# MC33886_driver_board.net
KiCad netlist of a schematic drawn in Altium Designer
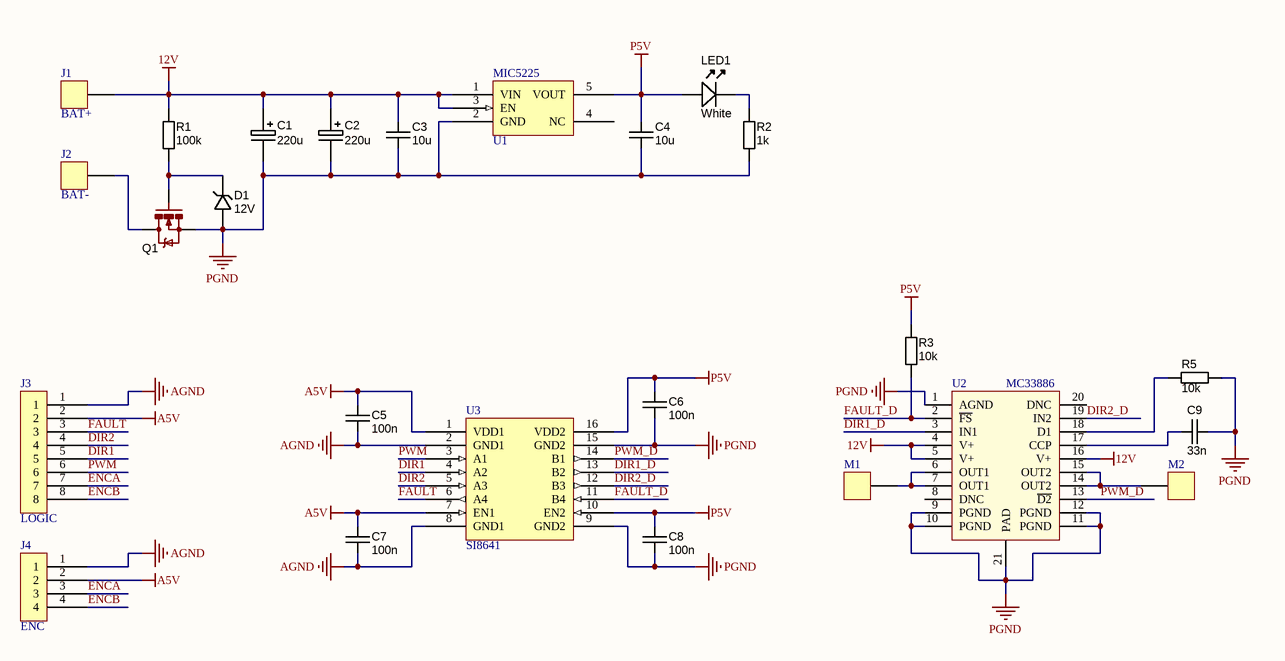
[diagram p0: MC33886_driver_board.SchDoc]

(export (version "E")
  (design (tool "Eeschema 10.0.6"))
  (components
    (comp (ref "C1")
      (value "220u")
      (footprint "CAPE3.5mm")
      (description "Capacitor THT Alum Elec 220uF 20% 16V")
      (fields (field (name "TOLERANCE") "±20%"))
      (libsource (lib "PBL - Capacitors") (part "CAPE_220u_16V_THD"))
    )
    (comp (ref "C2")
      (value "220u")
      (footprint "CAPE3.5mm")
      (description "Capacitor THT Alum Elec 220uF 20% 16V")
      (fields (field (name "TOLERANCE") "±20%"))
      (libsource (lib "PBL - Capacitors") (part "CAPE_220u_16V_THD"))
    )
    (comp (ref "C3")
      (value "10u")
      (footprint "CAPC3216X180N")
      (description "Capacitor SMD Cer 10uF 10% 16V X7R 1206")
      (fields (field (name "TOLERANCE") "±10%"))
      (libsource (lib "PBL - Capacitors") (part "CAPC_10u_1206_16V"))
    )
    (comp (ref "C4")
      (value "10u")
      (footprint "CAPC3216X180N")
      (description "Capacitor SMD Cer 10uF 10% 16V X7R 1206")
      (fields (field (name "TOLERANCE") "±10%"))
      (libsource (lib "PBL - Capacitors") (part "CAPC_10u_1206_16V"))
    )
    (comp (ref "C5")
      (value "100n")
      (footprint "CAPC1608X90N")
      (description "Capacitor SMD Cer 10nF 10% 50V X7R 0603")
      (fields (field (name "TOLERANCE") "±10%"))
      (libsource (lib "PBL - Capacitors") (part "CAPC_10n_0603_X7R_50V_10%"))
    )
    (comp (ref "C6")
      (value "100n")
      (footprint "CAPC1608X90N")
      (description "Capacitor SMD Cer 10nF 10% 50V X7R 0603")
      (fields (field (name "TOLERANCE") "±10%"))
      (libsource (lib "PBL - Capacitors") (part "CAPC_10n_0603_X7R_50V_10%"))
    )
    (comp (ref "C7")
      (value "100n")
      (footprint "CAPC1608X90N")
      (description "Capacitor SMD Cer 10nF 10% 50V X7R 0603")
      (fields (field (name "TOLERANCE") "±10%"))
      (libsource (lib "PBL - Capacitors") (part "CAPC_10n_0603_X7R_50V_10%"))
    )
    (comp (ref "C8")
      (value "100n")
      (footprint "CAPC1608X90N")
      (description "Capacitor SMD Cer 10nF 10% 50V X7R 0603")
      (fields (field (name "TOLERANCE") "±10%"))
      (libsource (lib "PBL - Capacitors") (part "CAPC_10n_0603_X7R_50V_10%"))
    )
    (comp (ref "C9")
      (value "33n")
      (footprint "CAPC1608X90N")
      (description "Capacitor SMD Cer 10nF 10% 50V X7R 0603")
      (fields (field (name "TOLERANCE") "±10%"))
      (libsource (lib "PBL - Capacitors") (part "CAPC_10n_0603_X7R_50V_10%"))
    )
    (comp (ref "D1")
      (value "12V")
      (footprint "SOD123")
      (description "Diode Zener SMD 28V 0.5W SOD-123")
      (fields (field (name "TOLERANCE") "±5%"))
      (libsource (lib "PBL - Diodes") (part "DIODE_ZENER_28V_500mW"))
    )
    (comp (ref "J1") (value "BAT+") (footprint "POWER-PAD") (libsource (lib "connectors") (part "HEADER-1")))
    (comp (ref "J2") (value "BAT-") (footprint "POWER-PAD") (libsource (lib "connectors") (part "HEADER-1")))
    (comp (ref "J3")
      (value "LOGIC")
      (footprint "MICRO-MATCH-8")
      (libsource (lib "connectors") (part "HEADER-8"))
    )
    (comp (ref "J4")
      (value "ENC")
      (footprint "MICRO-MATCH-4")
      (libsource (lib "connectors") (part "HEADER-4"))
    )
    (comp (ref "LED1")
      (value "White")
      (footprint "LED-0603-GREEN")
      (description "LED 0603 SMD Green 570nm 50mcd 20mA")
      (libsource (lib "PBL - Light Sources") (part "LED_SMD_Green_0603_570nm"))
    )
    (comp (ref "M1")
      (value "HEADER-1")
      (footprint "POWER-PAD")
      (libsource (lib "connectors") (part "HEADER-1"))
    )
    (comp (ref "M2") (value "HEADER-1") (footprint "POWER-PAD") (libsource (lib "") (part "HEADER-1_1")))
    (comp (ref "Q1") (value "MOSFET-N") (footprint "SOT669") (libsource (lib "mosfets") (part "MOSFET-N")))
    (comp (ref "R1")
      (value "100k")
      (footprint "RESC1608X55N")
      (description "Resistor SMD chip 1k Ohm 0.1W 1% 0603")
      (fields (field (name "TOLERANCE") "±1%"))
      (libsource (lib "PBL - Resistors") (part "RES_1K_0603_1%"))
    )
    (comp (ref "R2")
      (value "1k")
      (footprint "RESC1608X55N")
      (description "Resistor SMD chip 1k Ohm 0.1W 1% 0603")
      (fields (field (name "TOLERANCE") "±1%"))
      (libsource (lib "PBL - Resistors") (part "RES_1K_0603_1%"))
    )
    (comp (ref "R3")
      (value "10k")
      (footprint "RESC1608X55N")
      (description "Resistor SMD chip 1k Ohm 0.1W 1% 0603")
      (fields (field (name "TOLERANCE") "±1%"))
      (libsource (lib "PBL - Resistors") (part "RES_1K_0603_1%"))
    )
    (comp (ref "R5")
      (value "10k")
      (footprint "RESC1608X55N")
      (description "Resistor SMD chip 1k Ohm 0.1W 1% 0603")
      (fields (field (name "TOLERANCE") "±1%"))
      (libsource (lib "") (part "RES_1K_0603_1%_1"))
    )
    (comp (ref "U1") (value "MIC5225") (footprint "SOT23-5") (libsource (lib "power") (part "LDO-SOT23-5")))
    (comp (ref "U2")
      (value "MC33886")
      (footprint "MC33886")
      (libsource (lib "motor_drivers") (part "MC33886"))
    )
    (comp (ref "U3") (value "SI8641") (footprint "SOIC16") (libsource (lib "digital") (part "SI8641")))
  )
  (nets
    (net (code "1") (name "/DIR1") (class "Default")
      (node (ref "J3") (pin "5") (pinfunction "5_5") (pintype "passive"))
      (node (ref "U3") (pin "4") (pinfunction "A2_4") (pintype "input"))
    )
    (net (code "2") (name "/DIR1_D") (class "Default")
      (node (ref "U2") (pin "3") (pinfunction "IN1_3") (pintype "passive"))
      (node (ref "U3") (pin "13") (pinfunction "B2_13") (pintype "output"))
    )
    (net (code "3") (name "/DIR2") (class "Default")
      (node (ref "J3") (pin "4") (pinfunction "4_4") (pintype "passive"))
      (node (ref "U3") (pin "5") (pinfunction "A3_5") (pintype "input"))
    )
    (net (code "4") (name "/DIR2_D") (class "Default")
      (node (ref "U2") (pin "19") (pinfunction "IN2_19") (pintype "passive"))
      (node (ref "U3") (pin "12") (pinfunction "B3_12") (pintype "output"))
    )
    (net (code "5") (name "/ENCA") (class "Default")
      (node (ref "J3") (pin "7") (pinfunction "7_7") (pintype "passive"))
      (node (ref "J4") (pin "3") (pinfunction "3_3") (pintype "passive"))
    )
    (net (code "6") (name "/ENCB") (class "Default")
      (node (ref "J3") (pin "8") (pinfunction "8_8") (pintype "passive"))
      (node (ref "J4") (pin "4") (pinfunction "4_4") (pintype "passive"))
    )
    (net (code "7") (name "/FAULT") (class "Default")
      (node (ref "J3") (pin "3") (pinfunction "3_3") (pintype "passive"))
      (node (ref "U3") (pin "6") (pinfunction "A4_6") (pintype "output"))
    )
    (net (code "8") (name "/FAULT_D") (class "Default")
      (node (ref "R3") (pin "2") (pinfunction "2_2") (pintype "passive"))
      (node (ref "U2") (pin "2") (pinfunction "~{FS}_2") (pintype "passive"))
      (node (ref "U3") (pin "11") (pinfunction "B4_11") (pintype "input"))
    )
    (net (code "9") (name "/PWM") (class "Default")
      (node (ref "J3") (pin "6") (pinfunction "6_6") (pintype "passive"))
      (node (ref "U3") (pin "3") (pinfunction "A1_3") (pintype "input"))
    )
    (net (code "10") (name "/PWM_D") (class "Default")
      (node (ref "U2") (pin "13") (pinfunction "~{D2}_13") (pintype "passive"))
      (node (ref "U3") (pin "14") (pinfunction "B1_14") (pintype "output"))
    )
    (net (code "11") (name "12V") (class "Default")
      (node (ref "C1") (pin "1") (pintype "passive"))
      (node (ref "C2") (pin "1") (pintype "passive"))
      (node (ref "C3") (pin "1") (pintype "passive"))
      (node (ref "J1") (pin "1") (pinfunction "1_1") (pintype "passive"))
      (node (ref "R1") (pin "1") (pinfunction "1_1") (pintype "passive"))
      (node (ref "U1") (pin "1") (pinfunction "VIN_1") (pintype "power_in"))
      (node (ref "U1") (pin "3") (pinfunction "EN_3") (pintype "input"))
      (node (ref "U2") (pin "16") (pinfunction "V+_16") (pintype "passive"))
      (node (ref "U2") (pin "4") (pinfunction "V+_4") (pintype "passive"))
      (node (ref "U2") (pin "5") (pinfunction "V+_5") (pintype "passive"))
    )
    (net (code "12") (name "A5V") (class "Default")
      (node (ref "C5") (pin "2") (pintype "passive"))
      (node (ref "C7") (pin "2") (pintype "passive"))
      (node (ref "J3") (pin "2") (pinfunction "2_2") (pintype "passive"))
      (node (ref "J4") (pin "2") (pinfunction "2_2") (pintype "passive"))
      (node (ref "U3") (pin "1") (pinfunction "VDD1_1") (pintype "power_in"))
      (node (ref "U3") (pin "7") (pinfunction "EN1_7") (pintype "input"))
    )
    (net (code "13") (name "AGND") (class "Default")
      (node (ref "C5") (pin "1") (pintype "passive"))
      (node (ref "C7") (pin "1") (pintype "passive"))
      (node (ref "J3") (pin "1") (pinfunction "1_1") (pintype "passive"))
      (node (ref "J4") (pin "1") (pinfunction "1_1") (pintype "passive"))
      (node (ref "U3") (pin "2") (pinfunction "GND1_2") (pintype "power_in"))
      (node (ref "U3") (pin "8") (pinfunction "GND1_8") (pintype "power_in"))
    )
    (net (code "14") (name "Net-(D1-PadK)") (class "Default")
      (node (ref "D1") (pin "K") (pinfunction "K_K") (pintype "passive"))
      (node (ref "Q1") (pin "G") (pinfunction "G_G") (pintype "passive"))
      (node (ref "R1") (pin "2") (pinfunction "2_2") (pintype "passive"))
    )
    (net (code "15") (name "Net-(J2-Pad1)") (class "Default")
      (node (ref "J2") (pin "1") (pinfunction "1_1") (pintype "passive"))
      (node (ref "Q1") (pin "D") (pinfunction "D_D") (pintype "passive"))
    )
    (net (code "16") (name "Net-(LED1-PadK)") (class "Default")
      (node (ref "LED1") (pin "K") (pinfunction "K_K") (pintype "passive"))
      (node (ref "R2") (pin "1") (pinfunction "1_1") (pintype "passive"))
    )
    (net (code "17") (name "Net-(M1-Pad1)") (class "Default")
      (node (ref "M1") (pin "1") (pinfunction "1_1") (pintype "passive"))
      (node (ref "U2") (pin "6") (pinfunction "OUT1_6") (pintype "passive"))
      (node (ref "U2") (pin "7") (pinfunction "OUT1_7") (pintype "passive"))
    )
    (net (code "18") (name "Net-(M2-Pad1)") (class "Default")
      (node (ref "M2") (pin "1") (pinfunction "1_1") (pintype "passive"))
      (node (ref "U2") (pin "14") (pinfunction "OUT2_14") (pintype "passive"))
      (node (ref "U2") (pin "15") (pinfunction "OUT2_15") (pintype "passive"))
    )
    (net (code "19") (name "Net-(U2-CCP)") (class "Default")
      (node (ref "C9") (pin "1") (pintype "passive"))
      (node (ref "U2") (pin "17") (pinfunction "CCP_17") (pintype "passive"))
    )
    (net (code "20") (name "Net-(U2-D1)") (class "Default")
      (node (ref "R5") (pin "1") (pinfunction "1_1") (pintype "passive"))
      (node (ref "U2") (pin "18") (pinfunction "D1_18") (pintype "passive"))
    )
    (net (code "21") (name "P5V") (class "Default")
      (node (ref "C4") (pin "1") (pintype "passive"))
      (node (ref "C6") (pin "2") (pintype "passive"))
      (node (ref "C8") (pin "2") (pintype "passive"))
      (node (ref "LED1") (pin "A") (pinfunction "A_A") (pintype "passive"))
      (node (ref "R3") (pin "1") (pinfunction "1_1") (pintype "passive"))
      (node (ref "U1") (pin "5") (pinfunction "VOUT_5") (pintype "passive"))
      (node (ref "U3") (pin "10") (pinfunction "EN2_10") (pintype "input"))
      (node (ref "U3") (pin "16") (pinfunction "VDD2_16") (pintype "power_in"))
    )
    (net (code "22") (name "PGND") (class "Default")
      (node (ref "C1") (pin "2") (pintype "passive"))
      (node (ref "C2") (pin "2") (pintype "passive"))
      (node (ref "C3") (pin "2") (pintype "passive"))
      (node (ref "C4") (pin "2") (pintype "passive"))
      (node (ref "C6") (pin "1") (pintype "passive"))
      (node (ref "C8") (pin "1") (pintype "passive"))
      (node (ref "C9") (pin "2") (pintype "passive"))
      (node (ref "D1") (pin "A") (pinfunction "A_A") (pintype "passive"))
      (node (ref "Q1") (pin "S") (pinfunction "S_S") (pintype "passive"))
      (node (ref "R2") (pin "2") (pinfunction "2_2") (pintype "passive"))
      (node (ref "R5") (pin "2") (pinfunction "2_2") (pintype "passive"))
      (node (ref "U1") (pin "2") (pinfunction "GND_2") (pintype "power_in"))
      (node (ref "U2") (pin "1") (pinfunction "AGND_1") (pintype "passive"))
      (node (ref "U2") (pin "10") (pinfunction "PGND_10") (pintype "passive"))
      (node (ref "U2") (pin "11") (pinfunction "PGND_11") (pintype "passive"))
      (node (ref "U2") (pin "12") (pinfunction "PGND_12") (pintype "passive"))
      (node (ref "U2") (pin "21") (pinfunction "PAD_21") (pintype "passive"))
      (node (ref "U2") (pin "9") (pinfunction "PGND_9") (pintype "passive"))
      (node (ref "U3") (pin "15") (pinfunction "GND2_15") (pintype "power_in"))
      (node (ref "U3") (pin "9") (pinfunction "GND2_9") (pintype "power_in"))
    )
    (net (code "23") (name "unconnected-(U1-NC-Pad4)") (class "Default")
      (node (ref "U1") (pin "4") (pinfunction "NC_4") (pintype "power_in"))
    )
    (net (code "24") (name "unconnected-(U2-DNC-Pad8)") (class "Default")
      (node (ref "U2") (pin "8") (pinfunction "DNC_8") (pintype "passive"))
    )
    (net (code "25") (name "unconnected-(U2-DNC-Pad20)") (class "Default")
      (node (ref "U2") (pin "20") (pinfunction "DNC_20") (pintype "passive"))
    )
  )
)
